# usb_power_hub.net
KiCad netlist of a schematic drawn in EAGLE
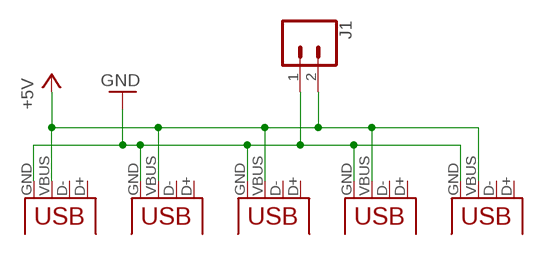
[diagram p0: schematic, sheet 1]

(export (version "E")
  (design (tool "Eeschema 10.0.6"))
  (components
    (comp (ref "J1")
      (value "CONN_025MM")
      (footprint "eagle-import:SCREWTERMINAL-5MM-2")
      (libsource (lib "eagle-import") (part "CONN_025MM"))
    )
    (comp (ref "X1")
      (value "USB-A-H")
      (footprint "eagle-import:USB-A-H")
      (libsource (lib "eagle-import") (part "USB-A-H"))
    )
    (comp (ref "X2")
      (value "USB-A-H")
      (footprint "eagle-import:USB-A-H")
      (libsource (lib "eagle-import") (part "USB-A-H"))
    )
    (comp (ref "X3")
      (value "USB-A-H")
      (footprint "eagle-import:USB-A-H")
      (libsource (lib "eagle-import") (part "USB-A-H"))
    )
    (comp (ref "X4")
      (value "USB-A-H")
      (footprint "eagle-import:USB-A-H")
      (libsource (lib "eagle-import") (part "USB-A-H"))
    )
    (comp (ref "X5")
      (value "USB-A-H")
      (footprint "eagle-import:USB-A-H")
      (libsource (lib "eagle-import") (part "USB-A-H"))
    )
  )
  (nets
    (net (code "1") (name "+5V") (class "Default")
      (node (ref "J1") (pin "2") (pinfunction "2_2") (pintype "passive"))
      (node (ref "X1") (pin "VBUS") (pinfunction "VBUS_VBUS") (pintype "bidirectional"))
      (node (ref "X2") (pin "VBUS") (pinfunction "VBUS_VBUS") (pintype "bidirectional"))
      (node (ref "X3") (pin "VBUS") (pinfunction "VBUS_VBUS") (pintype "bidirectional"))
      (node (ref "X4") (pin "VBUS") (pinfunction "VBUS_VBUS") (pintype "bidirectional"))
      (node (ref "X5") (pin "VBUS") (pinfunction "VBUS_VBUS") (pintype "bidirectional"))
    )
    (net (code "2") (name "GND") (class "Default")
      (node (ref "J1") (pin "1") (pinfunction "1_1") (pintype "passive"))
      (node (ref "X1") (pin "GND") (pinfunction "GND_GND") (pintype "bidirectional"))
      (node (ref "X2") (pin "GND") (pinfunction "GND_GND") (pintype "bidirectional"))
      (node (ref "X3") (pin "GND") (pinfunction "GND_GND") (pintype "bidirectional"))
      (node (ref "X4") (pin "GND") (pinfunction "GND_GND") (pintype "bidirectional"))
      (node (ref "X5") (pin "GND") (pinfunction "GND_GND") (pintype "bidirectional"))
    )
    (net (code "3") (name "unconnected-(X1-PadD+)") (class "Default")
      (node (ref "X1") (pin "D+") (pinfunction "D+_D+") (pintype "bidirectional"))
    )
    (net (code "4") (name "unconnected-(X1-PadD-)") (class "Default")
      (node (ref "X1") (pin "D-") (pinfunction "D-_D-") (pintype "bidirectional"))
    )
    (net (code "5") (name "unconnected-(X2-PadD+)") (class "Default")
      (node (ref "X2") (pin "D+") (pinfunction "D+_D+") (pintype "bidirectional"))
    )
    (net (code "6") (name "unconnected-(X2-PadD-)") (class "Default")
      (node (ref "X2") (pin "D-") (pinfunction "D-_D-") (pintype "bidirectional"))
    )
    (net (code "7") (name "unconnected-(X3-PadD+)") (class "Default")
      (node (ref "X3") (pin "D+") (pinfunction "D+_D+") (pintype "bidirectional"))
    )
    (net (code "8") (name "unconnected-(X3-PadD-)") (class "Default")
      (node (ref "X3") (pin "D-") (pinfunction "D-_D-") (pintype "bidirectional"))
    )
    (net (code "9") (name "unconnected-(X4-PadD+)") (class "Default")
      (node (ref "X4") (pin "D+") (pinfunction "D+_D+") (pintype "bidirectional"))
    )
    (net (code "10") (name "unconnected-(X4-PadD-)") (class "Default")
      (node (ref "X4") (pin "D-") (pinfunction "D-_D-") (pintype "bidirectional"))
    )
    (net (code "11") (name "unconnected-(X5-PadD+)") (class "Default")
      (node (ref "X5") (pin "D+") (pinfunction "D+_D+") (pintype "bidirectional"))
    )
    (net (code "12") (name "unconnected-(X5-PadD-)") (class "Default")
      (node (ref "X5") (pin "D-") (pinfunction "D-_D-") (pintype "bidirectional"))
    )
  )
)
